# AD9833_FG_Main_3V3.net
KiCad netlist of a schematic drawn in EAGLE
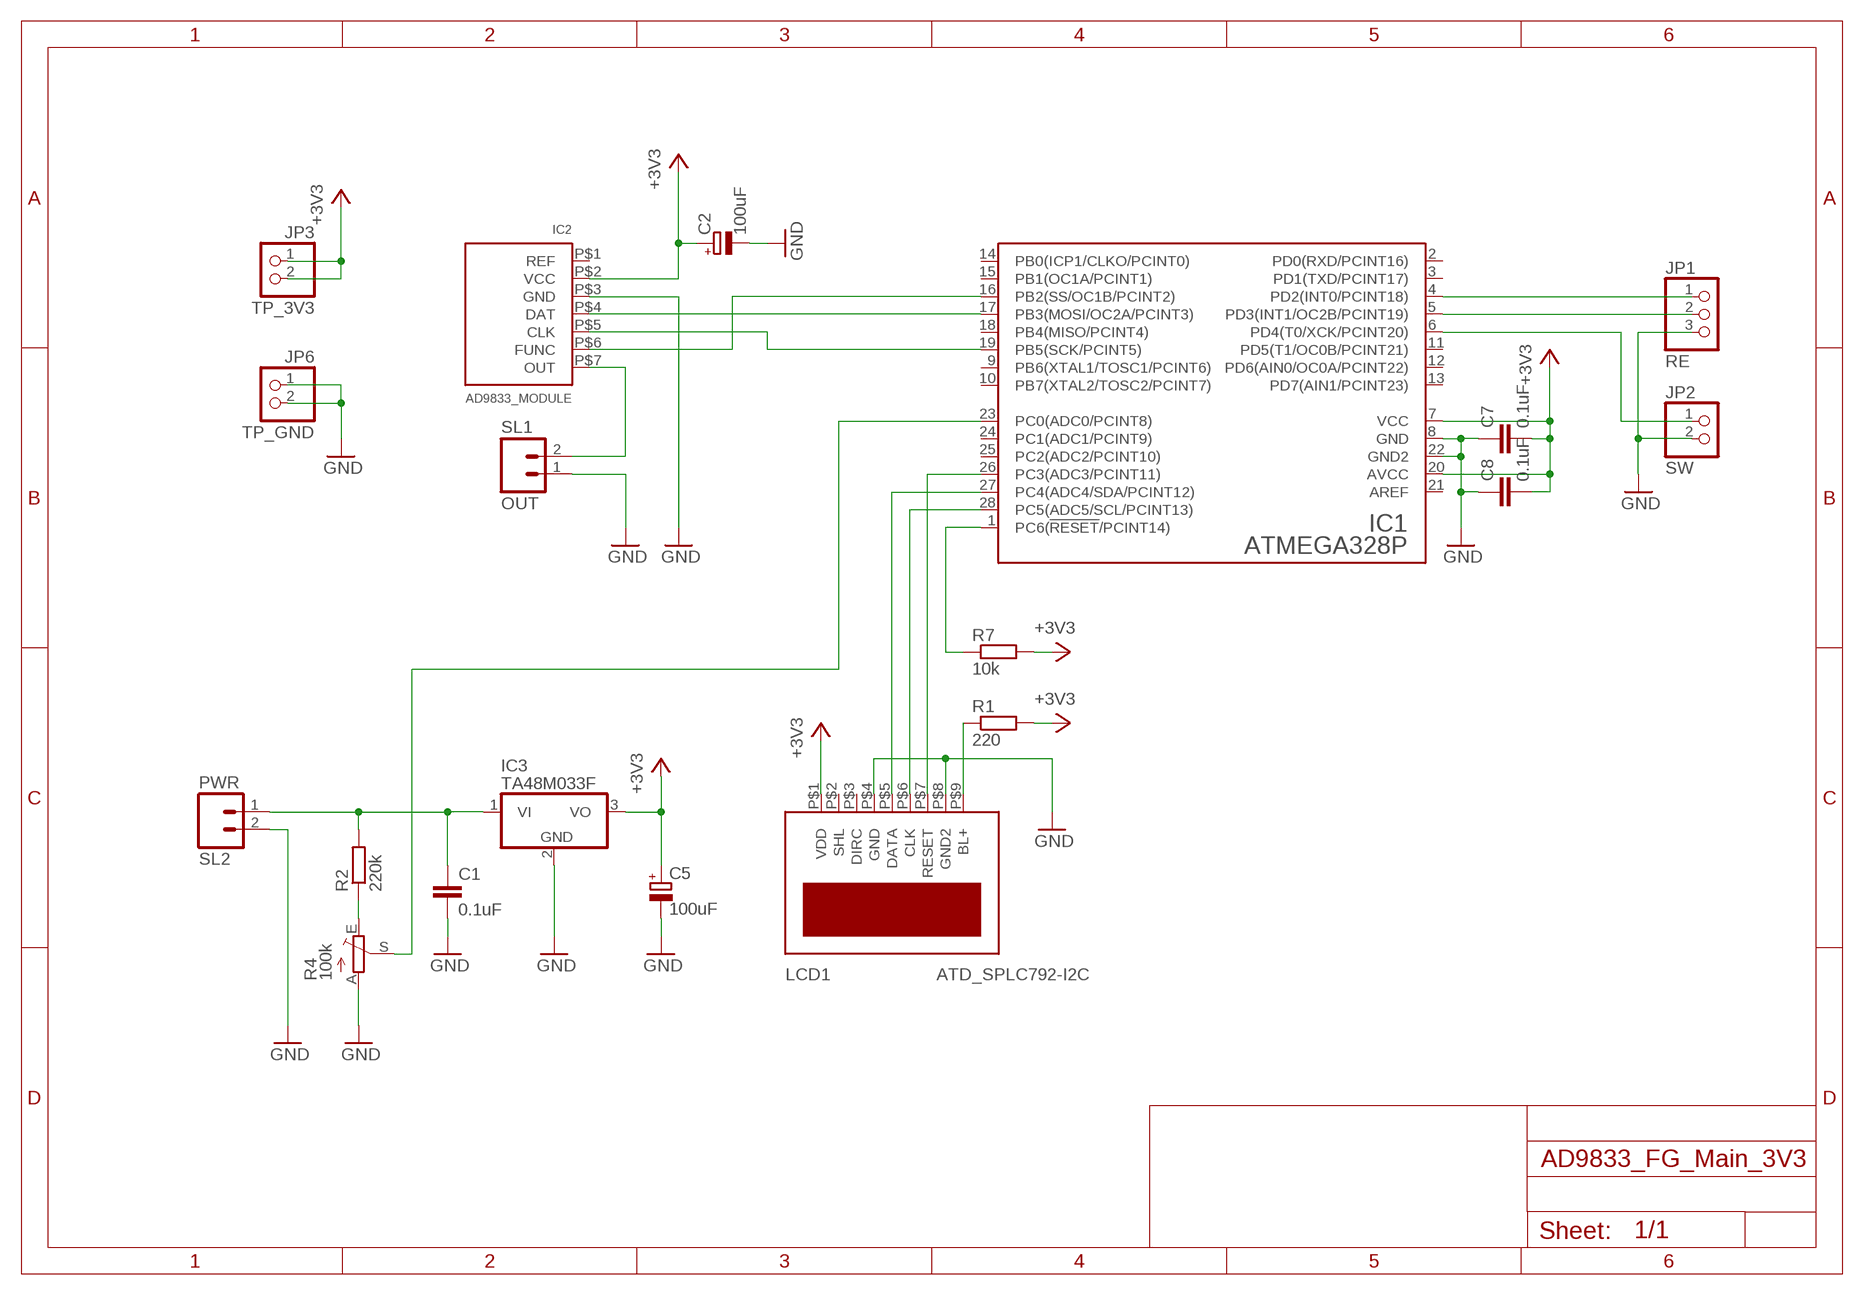
[diagram p0: schematic, sheet 1]

(export (version "E")
  (design (tool "Eeschema 10.0.6"))
  (components
    (comp (ref "C1")
      (value "0.1uF")
      (footprint "eagle-import:C025-024X044")
      (libsource (lib "eagle-import") (part "C-EU025-024X044"))
    )
    (comp (ref "C2")
      (value "100uF")
      (footprint "eagle-import:SANYO-OSCON_C")
      (libsource (lib "eagle-import") (part "CPOL-EUSANYO_C"))
    )
    (comp (ref "C5")
      (value "100uF")
      (footprint "eagle-import:E2,5-7")
      (libsource (lib "eagle-import") (part "CPOL-EUE2.5-7"))
    )
    (comp (ref "C7")
      (value "0.1uF")
      (footprint "eagle-import:C025-024X044")
      (libsource (lib "eagle-import") (part "C-EU025-024X044"))
    )
    (comp (ref "C8")
      (value "0.1uF")
      (footprint "eagle-import:C050-024X044")
      (libsource (lib "eagle-import") (part "C-EU050-024X044"))
    )
    (comp (ref "IC1")
      (value "ATMEGA328P")
      (footprint "eagle-import:DIL28-3")
      (libsource (lib "eagle-import") (part "ATMEGA48/88/168"))
    )
    (comp (ref "IC2")
      (value "AD9833_MODULE")
      (footprint "eagle-import:AD9833_MODULE")
      (libsource (lib "eagle-import") (part "AD9833_MODULE"))
    )
    (comp (ref "IC3")
      (value "TA48M033F")
      (footprint "eagle-import:TA48MXXX")
      (libsource (lib "eagle-import") (part "TA48M033F"))
    )
    (comp (ref "JP1")
      (value "RE")
      (footprint "eagle-import:1X03")
      (libsource (lib "eagle-import") (part "PINHD-1X3"))
    )
    (comp (ref "JP2")
      (value "SW")
      (footprint "eagle-import:1X02")
      (libsource (lib "eagle-import") (part "PINHD-1X2"))
    )
    (comp (ref "JP3")
      (value "TP_3V3")
      (footprint "eagle-import:1X02")
      (libsource (lib "eagle-import") (part "PINHD-1X2"))
    )
    (comp (ref "JP6")
      (value "TP_GND")
      (footprint "eagle-import:1X02")
      (libsource (lib "eagle-import") (part "PINHD-1X2"))
    )
    (comp (ref "LCD1")
      (value "ATD_SPLC792-I2C")
      (footprint "eagle-import:ATD_SPLC792-I2C")
      (libsource (lib "eagle-import") (part "ATD_SPLC792-I2C"))
    )
    (comp (ref "R1")
      (value "220")
      (footprint "eagle-import:0207_7")
      (libsource (lib "eagle-import") (part "R-EU_0207/7"))
    )
    (comp (ref "R2")
      (value "220k")
      (footprint "eagle-import:0207_7")
      (libsource (lib "eagle-import") (part "R-EU_0207/7"))
    )
    (comp (ref "R4")
      (value "100k")
      (footprint "eagle-import:B25P")
      (libsource (lib "eagle-import") (part "TRIM_EU-B25P"))
    )
    (comp (ref "R7")
      (value "10k")
      (footprint "eagle-import:0207_7")
      (libsource (lib "eagle-import") (part "R-EU_0207/7"))
    )
    (comp (ref "SL1")
      (value "OUT")
      (footprint "eagle-import:02P")
      (libsource (lib "eagle-import") (part "M02"))
    )
    (comp (ref "SL2")
      (value "PWR")
      (footprint "eagle-import:02P")
      (libsource (lib "eagle-import") (part "M02"))
    )
  )
  (nets
    (net (code "1") (name "+3V3") (class "Default")
      (node (ref "C2") (pin "+") (pinfunction "+_+") (pintype "passive"))
      (node (ref "C5") (pin "+") (pinfunction "+_+") (pintype "passive"))
      (node (ref "C7") (pin "2") (pinfunction "2_2") (pintype "passive"))
      (node (ref "C8") (pin "2") (pinfunction "2_2") (pintype "passive"))
      (node (ref "IC1") (pin "20") (pinfunction "AVCC_20") (pintype "power_in"))
      (node (ref "IC1") (pin "7") (pinfunction "VCC_7") (pintype "power_in"))
      (node (ref "IC2") (pin "P$2") (pinfunction "VCC_P$2") (pintype "power_in"))
      (node (ref "IC3") (pin "3") (pinfunction "VO_3") (pintype "passive"))
      (node (ref "JP3") (pin "1") (pinfunction "1_1") (pintype "passive"))
      (node (ref "JP3") (pin "2") (pinfunction "2_2") (pintype "passive"))
      (node (ref "LCD1") (pin "P$1") (pinfunction "VDD_P$1") (pintype "power_in"))
      (node (ref "R1") (pin "2") (pinfunction "2_2") (pintype "passive"))
      (node (ref "R7") (pin "2") (pinfunction "2_2") (pintype "passive"))
    )
    (net (code "2") (name "GND") (class "Default")
      (node (ref "C1") (pin "2") (pinfunction "2_2") (pintype "passive"))
      (node (ref "C2") (pin "-") (pinfunction "-_-") (pintype "passive"))
      (node (ref "C5") (pin "-") (pinfunction "-_-") (pintype "passive"))
      (node (ref "C7") (pin "1") (pinfunction "1_1") (pintype "passive"))
      (node (ref "C8") (pin "1") (pinfunction "1_1") (pintype "passive"))
      (node (ref "IC1") (pin "22") (pinfunction "GND2_22") (pintype "power_in"))
      (node (ref "IC1") (pin "8") (pinfunction "GND_8") (pintype "power_in"))
      (node (ref "IC2") (pin "P$3") (pinfunction "GND_P$3") (pintype "power_in"))
      (node (ref "IC3") (pin "2") (pinfunction "GND_2") (pintype "passive"))
      (node (ref "JP1") (pin "3") (pinfunction "3_3") (pintype "passive"))
      (node (ref "JP2") (pin "2") (pinfunction "2_2") (pintype "passive"))
      (node (ref "JP6") (pin "1") (pinfunction "1_1") (pintype "passive"))
      (node (ref "JP6") (pin "2") (pinfunction "2_2") (pintype "passive"))
      (node (ref "LCD1") (pin "P$4") (pinfunction "GND_P$4") (pintype "power_in"))
      (node (ref "LCD1") (pin "P$8") (pinfunction "GND2_P$8") (pintype "power_in"))
      (node (ref "R4") (pin "A") (pinfunction "A_A") (pintype "passive"))
      (node (ref "SL1") (pin "1") (pinfunction "1_1") (pintype "passive"))
      (node (ref "SL2") (pin "2") (pinfunction "2_2") (pintype "passive"))
    )
    (net (code "3") (name "Net-(IC1-PB2(SS{slash}OC1B{slash}PCINT2))") (class "Default")
      (node (ref "IC1") (pin "16") (pinfunction "PB2(SS/OC1B/PCINT2)_16") (pintype "bidirectional"))
      (node (ref "IC2") (pin "P$6") (pinfunction "FUNC_P$6") (pintype "input"))
    )
    (net (code "4") (name "Net-(IC1-PB3(MOSI{slash}OC2A{slash}PCINT3))") (class "Default")
      (node (ref "IC1") (pin "17") (pinfunction "PB3(MOSI/OC2A/PCINT3)_17") (pintype "bidirectional"))
      (node (ref "IC2") (pin "P$4") (pinfunction "DAT_P$4") (pintype "input"))
    )
    (net (code "5") (name "Net-(IC1-PB5(SCK{slash}PCINT5))") (class "Default")
      (node (ref "IC1") (pin "19") (pinfunction "PB5(SCK/PCINT5)_19") (pintype "bidirectional"))
      (node (ref "IC2") (pin "P$5") (pinfunction "CLK_P$5") (pintype "input"))
    )
    (net (code "6") (name "Net-(IC1-PC0(ADC0{slash}PCINT8))") (class "Default")
      (node (ref "IC1") (pin "23") (pinfunction "PC0(ADC0/PCINT8)_23") (pintype "bidirectional"))
      (node (ref "R4") (pin "S") (pinfunction "S_S") (pintype "passive"))
    )
    (net (code "7") (name "Net-(IC1-PC3(ADC3{slash}PCINT11))") (class "Default")
      (node (ref "IC1") (pin "26") (pinfunction "PC3(ADC3/PCINT11)_26") (pintype "bidirectional"))
      (node (ref "LCD1") (pin "P$7") (pinfunction "RESET_P$7") (pintype "input"))
    )
    (net (code "8") (name "Net-(IC1-PC4(ADC4{slash}SDA{slash}PCINT12))") (class "Default")
      (node (ref "IC1") (pin "27") (pinfunction "PC4(ADC4/SDA/PCINT12)_27") (pintype "bidirectional"))
      (node (ref "LCD1") (pin "P$5") (pinfunction "DATA_P$5") (pintype "bidirectional"))
    )
    (net (code "9") (name "Net-(IC1-PC5(ADC5{slash}SCL{slash}PCINT13))") (class "Default")
      (node (ref "IC1") (pin "28") (pinfunction "PC5(ADC5/SCL/PCINT13)_28") (pintype "bidirectional"))
      (node (ref "LCD1") (pin "P$6") (pinfunction "CLK_P$6") (pintype "input"))
    )
    (net (code "10") (name "Net-(IC1-PC6(~{RESET}{slash}PCINT14))") (class "Default")
      (node (ref "IC1") (pin "1") (pinfunction "PC6(~{RESET}/PCINT14)_1") (pintype "bidirectional"))
      (node (ref "R7") (pin "1") (pinfunction "1_1") (pintype "passive"))
    )
    (net (code "11") (name "Net-(IC1-PD2(INT0{slash}PCINT18))") (class "Default")
      (node (ref "IC1") (pin "4") (pinfunction "PD2(INT0/PCINT18)_4") (pintype "bidirectional"))
      (node (ref "JP1") (pin "1") (pinfunction "1_1") (pintype "passive"))
    )
    (net (code "12") (name "Net-(IC1-PD3(INT1{slash}OC2B{slash}PCINT19))") (class "Default")
      (node (ref "IC1") (pin "5") (pinfunction "PD3(INT1/OC2B/PCINT19)_5") (pintype "bidirectional"))
      (node (ref "JP1") (pin "2") (pinfunction "2_2") (pintype "passive"))
    )
    (net (code "13") (name "Net-(IC1-PD4(T0{slash}XCK{slash}PCINT20))") (class "Default")
      (node (ref "IC1") (pin "6") (pinfunction "PD4(T0/XCK/PCINT20)_6") (pintype "bidirectional"))
      (node (ref "JP2") (pin "1") (pinfunction "1_1") (pintype "passive"))
    )
    (net (code "14") (name "Net-(IC2-OUT)") (class "Default")
      (node (ref "IC2") (pin "P$7") (pinfunction "OUT_P$7") (pintype "output"))
      (node (ref "SL1") (pin "2") (pinfunction "2_2") (pintype "passive"))
    )
    (net (code "15") (name "Net-(IC3-VI)") (class "Default")
      (node (ref "C1") (pin "1") (pinfunction "1_1") (pintype "passive"))
      (node (ref "IC3") (pin "1") (pinfunction "VI_1") (pintype "input"))
      (node (ref "R2") (pin "2") (pinfunction "2_2") (pintype "passive"))
      (node (ref "SL2") (pin "1") (pinfunction "1_1") (pintype "passive"))
    )
    (net (code "16") (name "Net-(LCD1-BL+)") (class "Default")
      (node (ref "LCD1") (pin "P$9") (pinfunction "BL+_P$9") (pintype "power_in"))
      (node (ref "R1") (pin "1") (pinfunction "1_1") (pintype "passive"))
    )
    (net (code "17") (name "Net-(R2-Pad1)") (class "Default")
      (node (ref "R2") (pin "1") (pinfunction "1_1") (pintype "passive"))
      (node (ref "R4") (pin "E") (pinfunction "E_E") (pintype "passive"))
    )
    (net (code "18") (name "unconnected-(IC1-AREF-Pad21)") (class "Default")
      (node (ref "IC1") (pin "21") (pinfunction "AREF_21") (pintype "passive"))
    )
    (net (code "19") (name "unconnected-(IC1-PB0(ICP1{slash}CLKO{slash}PCINT0)-Pad14)") (class "Default")
      (node (ref "IC1") (pin "14") (pinfunction "PB0(ICP1/CLKO/PCINT0)_14") (pintype "bidirectional"))
    )
    (net (code "20") (name "unconnected-(IC1-PB1(OC1A{slash}PCINT1)-Pad15)") (class "Default")
      (node (ref "IC1") (pin "15") (pinfunction "PB1(OC1A/PCINT1)_15") (pintype "bidirectional"))
    )
    (net (code "21") (name "unconnected-(IC1-PB4(MISO{slash}PCINT4)-Pad18)") (class "Default")
      (node (ref "IC1") (pin "18") (pinfunction "PB4(MISO/PCINT4)_18") (pintype "bidirectional"))
    )
    (net (code "22") (name "unconnected-(IC1-PB6(XTAL1{slash}TOSC1{slash}PCINT6)-Pad9)") (class "Default")
      (node (ref "IC1") (pin "9") (pinfunction "PB6(XTAL1/TOSC1/PCINT6)_9") (pintype "bidirectional"))
    )
    (net (code "23") (name "unconnected-(IC1-PB7(XTAL2{slash}TOSC2{slash}PCINT7)-Pad10)") (class "Default")
      (node (ref "IC1") (pin "10") (pinfunction "PB7(XTAL2/TOSC2/PCINT7)_10") (pintype "bidirectional"))
    )
    (net (code "24") (name "unconnected-(IC1-PC1(ADC1{slash}PCINT9)-Pad24)") (class "Default")
      (node (ref "IC1") (pin "24") (pinfunction "PC1(ADC1/PCINT9)_24") (pintype "bidirectional"))
    )
    (net (code "25") (name "unconnected-(IC1-PC2(ADC2{slash}PCINT10)-Pad25)") (class "Default")
      (node (ref "IC1") (pin "25") (pinfunction "PC2(ADC2/PCINT10)_25") (pintype "bidirectional"))
    )
    (net (code "26") (name "unconnected-(IC1-PD0(RXD{slash}PCINT16)-Pad2)") (class "Default")
      (node (ref "IC1") (pin "2") (pinfunction "PD0(RXD/PCINT16)_2") (pintype "bidirectional"))
    )
    (net (code "27") (name "unconnected-(IC1-PD1(TXD{slash}PCINT17)-Pad3)") (class "Default")
      (node (ref "IC1") (pin "3") (pinfunction "PD1(TXD/PCINT17)_3") (pintype "bidirectional"))
    )
    (net (code "28") (name "unconnected-(IC1-PD5(T1{slash}OC0B{slash}PCINT21)-Pad11)") (class "Default")
      (node (ref "IC1") (pin "11") (pinfunction "PD5(T1/OC0B/PCINT21)_11") (pintype "bidirectional"))
    )
    (net (code "29") (name "unconnected-(IC1-PD6(AIN0{slash}OC0A{slash}PCINT22)-Pad12)") (class "Default")
      (node (ref "IC1") (pin "12") (pinfunction "PD6(AIN0/OC0A/PCINT22)_12") (pintype "bidirectional"))
    )
    (net (code "30") (name "unconnected-(IC1-PD7(AIN1{slash}PCINT23)-Pad13)") (class "Default")
      (node (ref "IC1") (pin "13") (pinfunction "PD7(AIN1/PCINT23)_13") (pintype "bidirectional"))
    )
    (net (code "31") (name "unconnected-(IC2-REF-PadP$1)") (class "Default")
      (node (ref "IC2") (pin "P$1") (pinfunction "REF_P$1") (pintype "no_connect"))
    )
    (net (code "32") (name "unconnected-(LCD1-DIRC-PadP$3)") (class "Default")
      (node (ref "LCD1") (pin "P$3") (pinfunction "DIRC_P$3") (pintype "no_connect"))
    )
    (net (code "33") (name "unconnected-(LCD1-SHL-PadP$2)") (class "Default")
      (node (ref "LCD1") (pin "P$2") (pinfunction "SHL_P$2") (pintype "no_connect"))
    )
  )
)
